# interfaces.net
KiCad netlist of a schematic drawn in Altium Designer
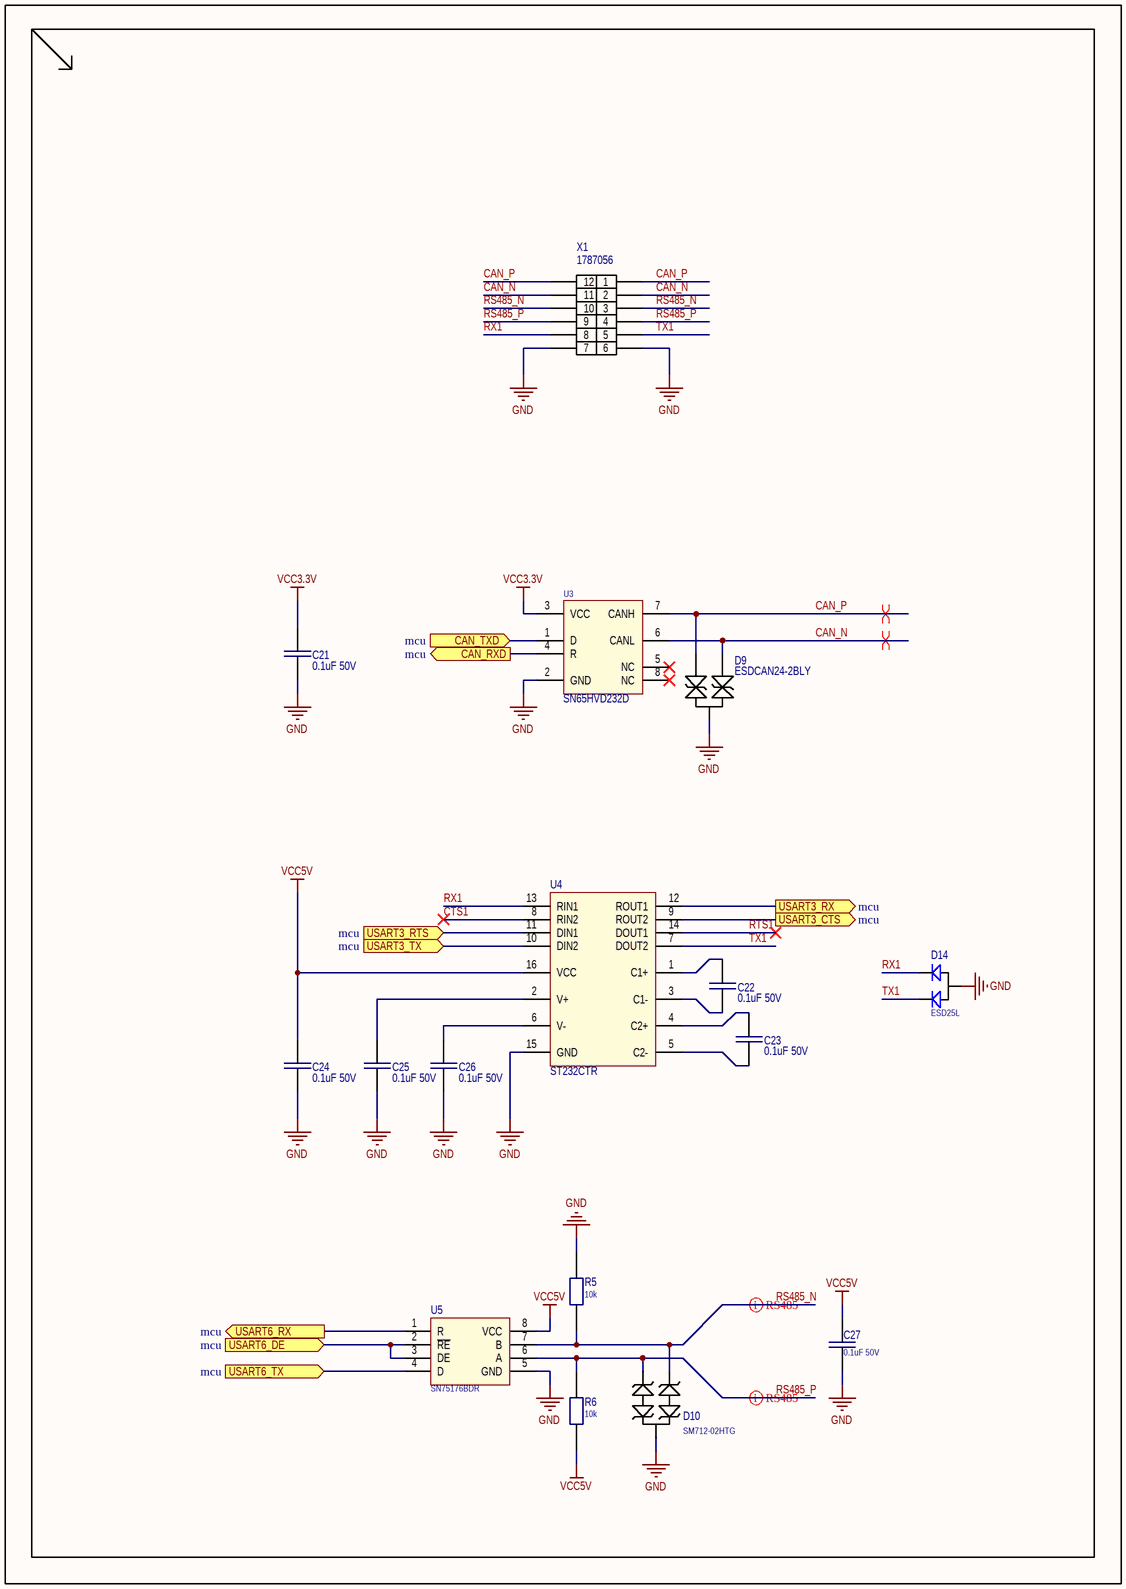
[diagram p0: interfaces.schdoc]

(export (version "E")
  (design (tool "Eeschema 10.0.6"))
  (components
    (comp (ref "C21")
      (value "0.1uF 50V")
      (footprint "C_0603")
      (description "Capacitor")
      (fields (field (name "PART") "CC0603KPX7R9BB104"))
      (libsource (lib "capacitors") (part "CAP_SMD"))
    )
    (comp (ref "C22")
      (value "0.1uF 50V")
      (footprint "C_0603")
      (description "Capacitor")
      (fields (field (name "PART") "CC0603KPX7R9BB104"))
      (libsource (lib "capacitors") (part "C0603"))
    )
    (comp (ref "C23")
      (value "0.1uF 50V")
      (footprint "C_0603")
      (description "Capacitor")
      (fields (field (name "PART") "CC0603KPX7R9BB104"))
      (libsource (lib "capacitors") (part "C0603"))
    )
    (comp (ref "C24")
      (value "0.1uF 50V")
      (footprint "C_0603")
      (description "Capacitor")
      (fields (field (name "PART") "CC0603KPX7R9BB104"))
      (libsource (lib "capacitors") (part "C0603"))
    )
    (comp (ref "C25")
      (value "0.1uF 50V")
      (footprint "C_0603")
      (description "Capacitor")
      (fields (field (name "PART") "CC0603KPX7R9BB104"))
      (libsource (lib "capacitors") (part "C0603"))
    )
    (comp (ref "C26")
      (value "0.1uF 50V")
      (footprint "C_0603")
      (description "Capacitor")
      (fields (field (name "PART") "CC0603KPX7R9BB104"))
      (libsource (lib "capacitors") (part "C0603"))
    )
    (comp (ref "C27")
      (value "0.1uF 50V")
      (footprint "C_0603")
      (description "Capacitor")
      (fields (field (name "PART") "CC0603KPX7R9BB104"))
      (libsource (lib "capacitors") (part "CAP_SMD"))
    )
    (comp (ref "D9")
      (value "ESDCAN24-2BLY")
      (footprint "diode:SOT23")
      (description "ESD")
      (libsource (lib "diode") (part "ESD_CAN"))
    )
    (comp (ref "D10")
      (value "SM712-02HTG")
      (footprint "diode:SOT23")
      (description "ESD")
      (libsource (lib "diode") (part "ESD"))
    )
    (comp (ref "D14")
      (value "ESD25L")
      (footprint "SOT23")
      (description "Diode")
      (fields (field (name "PART") "ESDA25L") (field (name "JLCPCBPART") "C95343"))
      (libsource (lib "diode") (part "TVS_SOT23"))
    )
    (comp (ref "R5")
      (value "10k")
      (footprint "R_0603")
      (description "Resistor")
      (fields (field (name "PART") "RC0603FR-0710KL"))
      (libsource (lib "resistors") (part "RES_SMD"))
    )
    (comp (ref "R6")
      (value "10k")
      (footprint "R_0603")
      (description "Resistor")
      (fields (field (name "PART") "RC0603FR-0710KL"))
      (libsource (lib "resistors") (part "RES_SMD"))
    )
    (comp (ref "U3")
      (value "SN65HVD232D")
      (footprint "SO-8_M")
      (description "CAN_transiever")
      (fields (field (name "PART") "SN65HVD232DR"))
      (libsource (lib "discret_ic") (part "SN65HVD232D"))
    )
    (comp (ref "U4")
      (value "ST232CTR")
      (footprint "TSSOP16_STM")
      (fields (field (name "COPYRIGHT") "Copyright (C) 2022 Ultra Librarian. All rights reserved."))
      (libsource (lib "discret_ic") (part "ST232CTR"))
    )
    (comp (ref "U5")
      (value "SN75176BDR")
      (footprint "SO-8")
      (description "RS485 Half Duplex Convertor")
      (libsource (lib "discret_ic") (part "SN75176BDR"))
    )
    (comp (ref "X1")
      (value "1787056")
      (footprint "DMC 1.5/ 6-G1F-3.5-LR P20THR 1787056")
      (description "THR-3.5-12P")
      (libsource (lib "connectors_socets") (part "15EDGRHCM-THR-3.5"))
    )
  )
  (nets
    (net (code "1") (name "/CAN_N") (class "Default")
      (node (ref "D9") (pin "2") (pinfunction "2_2") (pintype "passive"))
      (node (ref "U3") (pin "6") (pinfunction "CANL_6") (pintype "passive"))
      (node (ref "X1") (pin "11") (pinfunction "11_11") (pintype "passive"))
      (node (ref "X1") (pin "2") (pinfunction "2_2") (pintype "passive"))
    )
    (net (code "2") (name "/CAN_P") (class "Default")
      (node (ref "D9") (pin "1") (pinfunction "1_1") (pintype "passive"))
      (node (ref "U3") (pin "7") (pinfunction "CANH_7") (pintype "passive"))
      (node (ref "X1") (pin "1") (pinfunction "1_1") (pintype "passive"))
      (node (ref "X1") (pin "12") (pinfunction "12_12") (pintype "passive"))
    )
    (net (code "3") (name "/CAN_RXD") (class "Default")
      (node (ref "U3") (pin "4") (pinfunction "R_4") (pintype "passive"))
    )
    (net (code "4") (name "/CAN_TXD") (class "Default")
      (node (ref "U3") (pin "1") (pinfunction "D_1") (pintype "passive"))
    )
    (net (code "5") (name "/CTS1") (class "Default")
      (node (ref "U4") (pin "8") (pinfunction "RIN2_8") (pintype "passive+no_connect"))
    )
    (net (code "6") (name "/RS485_N") (class "Default")
      (node (ref "D10") (pin "1") (pinfunction "1_1") (pintype "passive"))
      (node (ref "R5") (pin "1") (pinfunction "1_1") (pintype "passive"))
      (node (ref "U5") (pin "7") (pinfunction "B_7") (pintype "passive"))
      (node (ref "X1") (pin "10") (pinfunction "10_10") (pintype "passive"))
      (node (ref "X1") (pin "3") (pinfunction "3_3") (pintype "passive"))
    )
    (net (code "7") (name "/RS485_P") (class "Default")
      (node (ref "D10") (pin "2") (pinfunction "2_2") (pintype "passive"))
      (node (ref "R6") (pin "2") (pinfunction "2_2") (pintype "passive"))
      (node (ref "U5") (pin "6") (pinfunction "A_6") (pintype "passive"))
      (node (ref "X1") (pin "4") (pinfunction "4_4") (pintype "passive"))
      (node (ref "X1") (pin "9") (pinfunction "9_9") (pintype "passive"))
    )
    (net (code "8") (name "/RTS1") (class "Default")
      (node (ref "U4") (pin "14") (pinfunction "DOUT1_14") (pintype "passive+no_connect"))
    )
    (net (code "9") (name "/RX1") (class "Default")
      (node (ref "D14") (pin "2") (pinfunction "2_2") (pintype "passive"))
      (node (ref "U4") (pin "13") (pinfunction "RIN1_13") (pintype "passive"))
      (node (ref "X1") (pin "8") (pinfunction "8_8") (pintype "passive"))
    )
    (net (code "10") (name "/TX1") (class "Default")
      (node (ref "D14") (pin "1") (pinfunction "1_1") (pintype "passive"))
      (node (ref "U4") (pin "7") (pinfunction "DOUT2_7") (pintype "passive"))
      (node (ref "X1") (pin "5") (pinfunction "5_5") (pintype "passive"))
    )
    (net (code "11") (name "/USART3_CTS") (class "Default")
      (node (ref "U4") (pin "9") (pinfunction "ROUT2_9") (pintype "passive"))
    )
    (net (code "12") (name "/USART3_RTS") (class "Default")
      (node (ref "U4") (pin "11") (pinfunction "DIN1_11") (pintype "passive"))
    )
    (net (code "13") (name "/USART3_RX") (class "Default")
      (node (ref "U4") (pin "12") (pinfunction "ROUT1_12") (pintype "passive"))
    )
    (net (code "14") (name "/USART3_TX") (class "Default")
      (node (ref "U4") (pin "10") (pinfunction "DIN2_10") (pintype "passive"))
    )
    (net (code "15") (name "/USART6_DE") (class "Default")
      (node (ref "U5") (pin "2") (pinfunction "~{RE}_2") (pintype "passive"))
      (node (ref "U5") (pin "3") (pinfunction "DE_3") (pintype "passive"))
    )
    (net (code "16") (name "/USART6_RX") (class "Default")
      (node (ref "U5") (pin "1") (pinfunction "R_1") (pintype "passive"))
    )
    (net (code "17") (name "/USART6_TX") (class "Default")
      (node (ref "U5") (pin "4") (pinfunction "D_4") (pintype "passive"))
    )
    (net (code "18") (name "GND") (class "Default")
      (node (ref "C21") (pin "1") (pinfunction "1_1") (pintype "passive"))
      (node (ref "C24") (pin "1") (pinfunction "1_1") (pintype "passive"))
      (node (ref "C25") (pin "1") (pinfunction "1_1") (pintype "passive"))
      (node (ref "C26") (pin "1") (pinfunction "1_1") (pintype "passive"))
      (node (ref "C27") (pin "1") (pinfunction "1_1") (pintype "passive"))
      (node (ref "D10") (pin "3") (pinfunction "3_3") (pintype "passive"))
      (node (ref "D14") (pin "3") (pinfunction "3_3") (pintype "passive"))
      (node (ref "D9") (pin "3") (pinfunction "3_3") (pintype "passive"))
      (node (ref "R5") (pin "2") (pinfunction "2_2") (pintype "passive"))
      (node (ref "U3") (pin "2") (pinfunction "GND_2") (pintype "passive"))
      (node (ref "U4") (pin "15") (pinfunction "GND_15") (pintype "passive"))
      (node (ref "U5") (pin "5") (pinfunction "GND_5") (pintype "passive"))
      (node (ref "X1") (pin "6") (pinfunction "6_6") (pintype "passive"))
      (node (ref "X1") (pin "7") (pinfunction "7_7") (pintype "passive"))
    )
    (net (code "19") (name "Net-(U4-C1+)") (class "Default")
      (node (ref "C22") (pin "1") (pinfunction "1_1") (pintype "passive"))
      (node (ref "U4") (pin "1") (pinfunction "C1+_1") (pintype "passive"))
    )
    (net (code "20") (name "Net-(U4-C1-)") (class "Default")
      (node (ref "C22") (pin "2") (pinfunction "2_2") (pintype "passive"))
      (node (ref "U4") (pin "3") (pinfunction "C1-_3") (pintype "passive"))
    )
    (net (code "21") (name "Net-(U4-C2+)") (class "Default")
      (node (ref "C23") (pin "1") (pinfunction "1_1") (pintype "passive"))
      (node (ref "U4") (pin "4") (pinfunction "C2+_4") (pintype "passive"))
    )
    (net (code "22") (name "Net-(U4-C2-)") (class "Default")
      (node (ref "C23") (pin "2") (pinfunction "2_2") (pintype "passive"))
      (node (ref "U4") (pin "5") (pinfunction "C2-_5") (pintype "passive"))
    )
    (net (code "23") (name "Net-(U4-V+)") (class "Default")
      (node (ref "C25") (pin "2") (pinfunction "2_2") (pintype "passive"))
      (node (ref "U4") (pin "2") (pinfunction "V+_2") (pintype "passive"))
    )
    (net (code "24") (name "Net-(U4-V-)") (class "Default")
      (node (ref "C26") (pin "2") (pinfunction "2_2") (pintype "passive"))
      (node (ref "U4") (pin "6") (pinfunction "V-_6") (pintype "passive"))
    )
    (net (code "25") (name "VCC3.3V") (class "Default")
      (node (ref "C21") (pin "2") (pinfunction "2_2") (pintype "passive"))
      (node (ref "U3") (pin "3") (pinfunction "VCC_3") (pintype "passive"))
    )
    (net (code "26") (name "VCC5V") (class "Default")
      (node (ref "C24") (pin "2") (pinfunction "2_2") (pintype "passive"))
      (node (ref "C27") (pin "2") (pinfunction "2_2") (pintype "passive"))
      (node (ref "R6") (pin "1") (pinfunction "1_1") (pintype "passive"))
      (node (ref "U4") (pin "16") (pinfunction "VCC_16") (pintype "passive"))
      (node (ref "U5") (pin "8") (pinfunction "VCC_8") (pintype "passive"))
    )
    (net (code "27") (name "unconnected-(U3-NC-Pad5)") (class "Default")
      (node (ref "U3") (pin "5") (pinfunction "NC_5") (pintype "passive+no_connect"))
    )
    (net (code "28") (name "unconnected-(U3-NC-Pad8)") (class "Default")
      (node (ref "U3") (pin "8") (pinfunction "NC_8") (pintype "passive+no_connect"))
    )
  )
)
